# GIP-DHT11.net
KiCad netlist of a schematic drawn in EAGLE
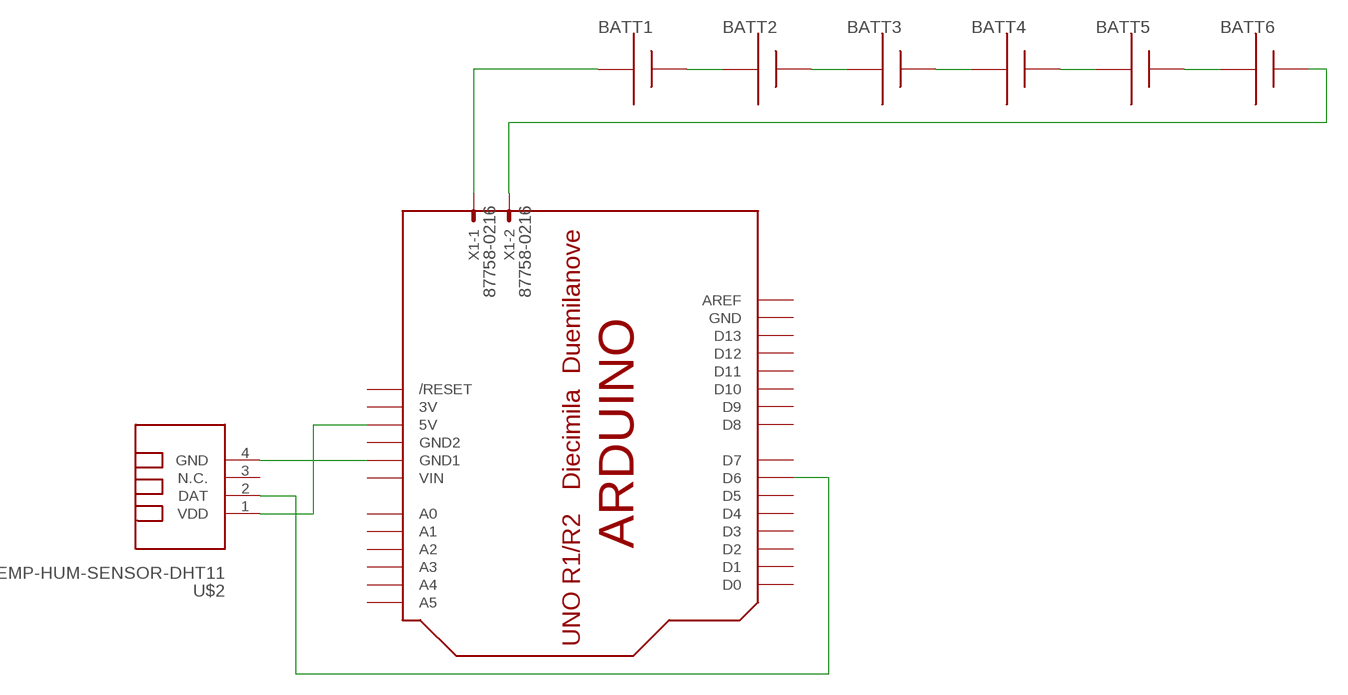
[diagram p0: schematic, sheet 1]

(export (version "E")
  (design (tool "Eeschema 10.0.6"))
  (components
    (comp (ref "BATT1")
      (value "AAA")
      (footprint "eagle-import:12BH412")
      (libsource (lib "eagle-import") (part "AAA"))
    )
    (comp (ref "BATT2")
      (value "AAA")
      (footprint "eagle-import:12BH412")
      (libsource (lib "eagle-import") (part "AAA"))
    )
    (comp (ref "BATT3")
      (value "AAA")
      (footprint "eagle-import:12BH412")
      (libsource (lib "eagle-import") (part "AAA"))
    )
    (comp (ref "BATT4")
      (value "AAA")
      (footprint "eagle-import:12BH412")
      (libsource (lib "eagle-import") (part "AAA"))
    )
    (comp (ref "BATT5")
      (value "AAA")
      (footprint "eagle-import:12BH412")
      (libsource (lib "eagle-import") (part "AAA"))
    )
    (comp (ref "BATT6")
      (value "AAA")
      (footprint "eagle-import:12BH412")
      (libsource (lib "eagle-import") (part "AAA"))
    )
    (comp (ref "U$1")
      (value "ARDUINO-BPLACE")
      (footprint "eagle-import:ARDUINO-BPLACE")
      (libsource (lib "eagle-import") (part "ARDUINO-BPLACE"))
    )
    (comp (ref "U$2")
      (value "TEMP-HUM-SENSOR-DHT11")
      (footprint "eagle-import:TEMP-HUM-SENSOR-DHT11")
      (libsource (lib "eagle-import") (part "TEMP-HUM-SENSOR-DHT11"))
    )
    (comp (ref "X1")
      (value "87758-0216")
      (footprint "eagle-import:87758-0216")
      (fields (field (name "MF") "MOLEX"))
      (libsource (lib "eagle-import") (part "87758-0216"))
    )
  )
  (nets
    (net (code "1") (name "/3V") (class "Default")
      (node (ref "U$1") (pin "3V") (pinfunction "3V_3V") (pintype "power_in"))
    )
    (net (code "2") (name "/GND") (class "Default")
      (node (ref "U$1") (pin "GND") (pinfunction "GND_GND") (pintype "power_in"))
    )
    (net (code "3") (name "/GND2") (class "Default")
      (node (ref "U$1") (pin "GND2") (pinfunction "GND2_GND2") (pintype "power_in"))
    )
    (net (code "4") (name "/VIN") (class "Default")
      (node (ref "U$1") (pin "VIN") (pinfunction "VIN_VIN") (pintype "power_in"))
    )
    (net (code "5") (name "Net-(BATT1-Pad+)") (class "Default")
      (node (ref "BATT1") (pin "+") (pinfunction "+_+") (pintype "bidirectional"))
      (node (ref "BATT2") (pin "-") (pinfunction "-_-") (pintype "bidirectional"))
    )
    (net (code "6") (name "Net-(BATT2-Pad+)") (class "Default")
      (node (ref "BATT2") (pin "+") (pinfunction "+_+") (pintype "bidirectional"))
      (node (ref "BATT3") (pin "-") (pinfunction "-_-") (pintype "bidirectional"))
    )
    (net (code "7") (name "Net-(BATT3-Pad+)") (class "Default")
      (node (ref "BATT3") (pin "+") (pinfunction "+_+") (pintype "bidirectional"))
      (node (ref "BATT4") (pin "-") (pinfunction "-_-") (pintype "bidirectional"))
    )
    (net (code "8") (name "Net-(BATT4-Pad+)") (class "Default")
      (node (ref "BATT4") (pin "+") (pinfunction "+_+") (pintype "bidirectional"))
      (node (ref "BATT5") (pin "-") (pinfunction "-_-") (pintype "bidirectional"))
    )
    (net (code "9") (name "Net-(BATT5-Pad+)") (class "Default")
      (node (ref "BATT5") (pin "+") (pinfunction "+_+") (pintype "bidirectional"))
      (node (ref "BATT6") (pin "-") (pinfunction "-_-") (pintype "bidirectional"))
    )
    (net (code "10") (name "Net-(U$2-DAT)") (class "Default")
      (node (ref "U$1") (pin "D6") (pinfunction "D6_D6") (pintype "bidirectional"))
      (node (ref "U$2") (pin "2") (pinfunction "DAT_2") (pintype "bidirectional"))
    )
    (net (code "11") (name "Net-(U$2-GND)") (class "Default")
      (node (ref "U$1") (pin "GND1") (pinfunction "GND1_GND1") (pintype "power_in"))
      (node (ref "U$2") (pin "4") (pinfunction "GND_4") (pintype "power_in"))
    )
    (net (code "12") (name "Net-(U$2-VDD)") (class "Default")
      (node (ref "U$1") (pin "5V") (pinfunction "5V_5V") (pintype "power_in"))
      (node (ref "U$2") (pin "1") (pinfunction "VDD_1") (pintype "power_in"))
    )
    (net (code "13") (name "Net-(X1A-S)") (class "Default")
      (node (ref "BATT1") (pin "-") (pinfunction "-_-") (pintype "bidirectional"))
      (node (ref "X1") (pin "1") (pinfunction "S_1") (pintype "passive"))
    )
    (net (code "14") (name "Net-(X1B-S)") (class "Default")
      (node (ref "BATT6") (pin "+") (pinfunction "+_+") (pintype "bidirectional"))
      (node (ref "X1") (pin "2") (pinfunction "S_2") (pintype "passive"))
    )
    (net (code "15") (name "unconnected-(U$1-PadA0)") (class "Default")
      (node (ref "U$1") (pin "A0") (pinfunction "A0_A0") (pintype "bidirectional"))
    )
    (net (code "16") (name "unconnected-(U$1-PadA1)") (class "Default")
      (node (ref "U$1") (pin "A1") (pinfunction "A1_A1") (pintype "bidirectional"))
    )
    (net (code "17") (name "unconnected-(U$1-PadA2)") (class "Default")
      (node (ref "U$1") (pin "A2") (pinfunction "A2_A2") (pintype "bidirectional"))
    )
    (net (code "18") (name "unconnected-(U$1-PadA3)") (class "Default")
      (node (ref "U$1") (pin "A3") (pinfunction "A3_A3") (pintype "bidirectional"))
    )
    (net (code "19") (name "unconnected-(U$1-PadA4)") (class "Default")
      (node (ref "U$1") (pin "A4") (pinfunction "A4_A4") (pintype "bidirectional"))
    )
    (net (code "20") (name "unconnected-(U$1-PadA5)") (class "Default")
      (node (ref "U$1") (pin "A5") (pinfunction "A5_A5") (pintype "bidirectional"))
    )
    (net (code "21") (name "unconnected-(U$1-PadAREF)") (class "Default")
      (node (ref "U$1") (pin "AREF") (pinfunction "AREF_AREF") (pintype "bidirectional"))
    )
    (net (code "22") (name "unconnected-(U$1-PadD0)") (class "Default")
      (node (ref "U$1") (pin "D0") (pinfunction "D0_D0") (pintype "bidirectional"))
    )
    (net (code "23") (name "unconnected-(U$1-PadD1)") (class "Default")
      (node (ref "U$1") (pin "D1") (pinfunction "D1_D1") (pintype "bidirectional"))
    )
    (net (code "24") (name "unconnected-(U$1-PadD2)") (class "Default")
      (node (ref "U$1") (pin "D2") (pinfunction "D2_D2") (pintype "bidirectional"))
    )
    (net (code "25") (name "unconnected-(U$1-PadD3)") (class "Default")
      (node (ref "U$1") (pin "D3") (pinfunction "D3_D3") (pintype "bidirectional"))
    )
    (net (code "26") (name "unconnected-(U$1-PadD4)") (class "Default")
      (node (ref "U$1") (pin "D4") (pinfunction "D4_D4") (pintype "bidirectional"))
    )
    (net (code "27") (name "unconnected-(U$1-PadD5)") (class "Default")
      (node (ref "U$1") (pin "D5") (pinfunction "D5_D5") (pintype "bidirectional"))
    )
    (net (code "28") (name "unconnected-(U$1-PadD7)") (class "Default")
      (node (ref "U$1") (pin "D7") (pinfunction "D7_D7") (pintype "bidirectional"))
    )
    (net (code "29") (name "unconnected-(U$1-PadD8)") (class "Default")
      (node (ref "U$1") (pin "D8") (pinfunction "D8_D8") (pintype "bidirectional"))
    )
    (net (code "30") (name "unconnected-(U$1-PadD9)") (class "Default")
      (node (ref "U$1") (pin "D9") (pinfunction "D9_D9") (pintype "bidirectional"))
    )
    (net (code "31") (name "unconnected-(U$1-PadD10)") (class "Default")
      (node (ref "U$1") (pin "D10") (pinfunction "D10_D10") (pintype "bidirectional"))
    )
    (net (code "32") (name "unconnected-(U$1-PadD11)") (class "Default")
      (node (ref "U$1") (pin "D11") (pinfunction "D11_D11") (pintype "bidirectional"))
    )
    (net (code "33") (name "unconnected-(U$1-PadD12)") (class "Default")
      (node (ref "U$1") (pin "D12") (pinfunction "D12_D12") (pintype "bidirectional"))
    )
    (net (code "34") (name "unconnected-(U$1-PadD13)") (class "Default")
      (node (ref "U$1") (pin "D13") (pinfunction "D13_D13") (pintype "bidirectional"))
    )
    (net (code "35") (name "unconnected-(U$1-{slash}RESET-PadRESET)") (class "Default")
      (node (ref "U$1") (pin "RESET") (pinfunction "/RESET_RESET") (pintype "bidirectional"))
    )
    (net (code "36") (name "unconnected-(U$2-N.C.-Pad3)") (class "Default")
      (node (ref "U$2") (pin "3") (pinfunction "N.C._3") (pintype "passive"))
    )
  )
)
